# Works_007.net
KiCad netlist of a schematic drawn in EAGLE
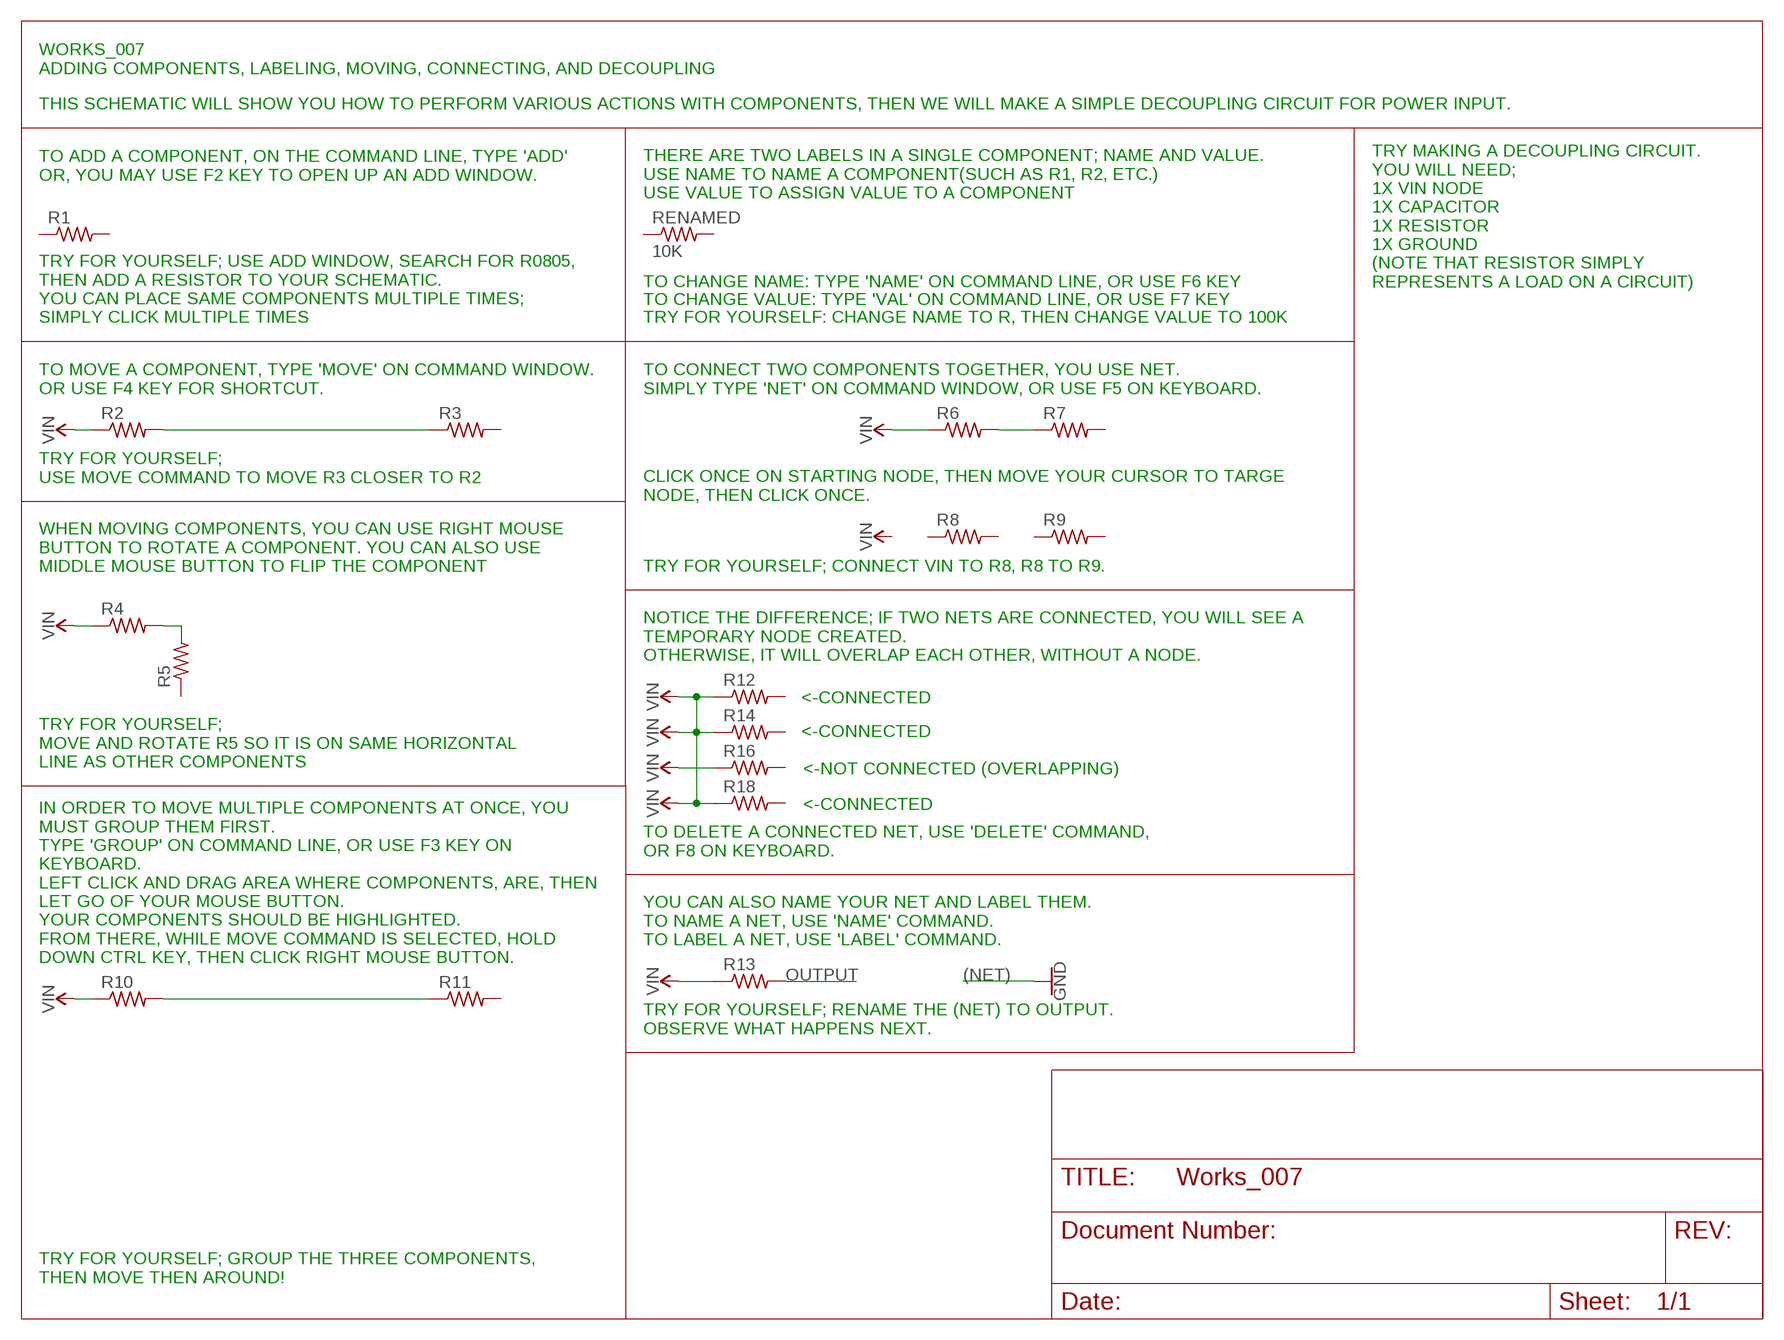
[diagram p0: schematic, sheet 1]

(export (version "E")
  (design (tool "Eeschema 10.0.6"))
  (components
    (comp (ref "R1")
      (value "R-US_R0805")
      (footprint "eagle-import:R0805")
      (libsource (lib "eagle-import") (part "R-US_R0805"))
    )
    (comp (ref "R2")
      (value "R-US_R0805")
      (footprint "eagle-import:R0805")
      (libsource (lib "eagle-import") (part "R-US_R0805"))
    )
    (comp (ref "R3")
      (value "R-US_R0805")
      (footprint "eagle-import:R0805")
      (libsource (lib "eagle-import") (part "R-US_R0805"))
    )
    (comp (ref "R4")
      (value "R-US_R0805")
      (footprint "eagle-import:R0805")
      (libsource (lib "eagle-import") (part "R-US_R0805"))
    )
    (comp (ref "R5")
      (value "R-US_R0805")
      (footprint "eagle-import:R0805")
      (libsource (lib "eagle-import") (part "R-US_R0805"))
    )
    (comp (ref "R6")
      (value "R-US_R0805")
      (footprint "eagle-import:R0805")
      (libsource (lib "eagle-import") (part "R-US_R0805"))
    )
    (comp (ref "R7")
      (value "R-US_R0805")
      (footprint "eagle-import:R0805")
      (libsource (lib "eagle-import") (part "R-US_R0805"))
    )
    (comp (ref "R8")
      (value "R-US_R0805")
      (footprint "eagle-import:R0805")
      (libsource (lib "eagle-import") (part "R-US_R0805"))
    )
    (comp (ref "R9")
      (value "R-US_R0805")
      (footprint "eagle-import:R0805")
      (libsource (lib "eagle-import") (part "R-US_R0805"))
    )
    (comp (ref "R10")
      (value "R-US_R0805")
      (footprint "eagle-import:R0805")
      (libsource (lib "eagle-import") (part "R-US_R0805"))
    )
    (comp (ref "R11")
      (value "R-US_R0805")
      (footprint "eagle-import:R0805")
      (libsource (lib "eagle-import") (part "R-US_R0805"))
    )
    (comp (ref "R12")
      (value "R-US_R0805")
      (footprint "eagle-import:R0805")
      (libsource (lib "eagle-import") (part "R-US_R0805"))
    )
    (comp (ref "R13")
      (value "R-US_R0805")
      (footprint "eagle-import:R0805")
      (libsource (lib "eagle-import") (part "R-US_R0805"))
    )
    (comp (ref "R14")
      (value "R-US_R0805")
      (footprint "eagle-import:R0805")
      (libsource (lib "eagle-import") (part "R-US_R0805"))
    )
    (comp (ref "R16")
      (value "R-US_R0805")
      (footprint "eagle-import:R0805")
      (libsource (lib "eagle-import") (part "R-US_R0805"))
    )
    (comp (ref "R18")
      (value "R-US_R0805")
      (footprint "eagle-import:R0805")
      (libsource (lib "eagle-import") (part "R-US_R0805"))
    )
    (comp (ref "RENAMED")
      (value "10K")
      (footprint "eagle-import:R0805")
      (libsource (lib "eagle-import") (part "R-US_R0805"))
    )
  )
  (nets
    (net (code "1") (name "/OUTPUT") (class "Default")
      (node (ref "R13") (pin "2") (pinfunction "2_2") (pintype "passive"))
    )
    (net (code "3") (name "Net-(R2-Pad2)") (class "Default")
      (node (ref "R2") (pin "2") (pinfunction "2_2") (pintype "passive"))
      (node (ref "R3") (pin "1") (pinfunction "1_1") (pintype "passive"))
    )
    (net (code "4") (name "Net-(R4-Pad2)") (class "Default")
      (node (ref "R4") (pin "2") (pinfunction "2_2") (pintype "passive"))
      (node (ref "R5") (pin "2") (pinfunction "2_2") (pintype "passive"))
    )
    (net (code "5") (name "Net-(R6-Pad2)") (class "Default")
      (node (ref "R6") (pin "2") (pinfunction "2_2") (pintype "passive"))
      (node (ref "R7") (pin "1") (pinfunction "1_1") (pintype "passive"))
    )
    (net (code "6") (name "Net-(R10-Pad2)") (class "Default")
      (node (ref "R10") (pin "2") (pinfunction "2_2") (pintype "passive"))
      (node (ref "R11") (pin "1") (pinfunction "1_1") (pintype "passive"))
    )
    (net (code "7") (name "VIN") (class "Default")
      (node (ref "R10") (pin "1") (pinfunction "1_1") (pintype "passive"))
      (node (ref "R12") (pin "1") (pinfunction "1_1") (pintype "passive"))
      (node (ref "R13") (pin "1") (pinfunction "1_1") (pintype "passive"))
      (node (ref "R14") (pin "1") (pinfunction "1_1") (pintype "passive"))
      (node (ref "R16") (pin "1") (pinfunction "1_1") (pintype "passive"))
      (node (ref "R18") (pin "1") (pinfunction "1_1") (pintype "passive"))
      (node (ref "R2") (pin "1") (pinfunction "1_1") (pintype "passive"))
      (node (ref "R4") (pin "1") (pinfunction "1_1") (pintype "passive"))
      (node (ref "R6") (pin "1") (pinfunction "1_1") (pintype "passive"))
    )
    (net (code "8") (name "unconnected-(R1-Pad1)") (class "Default")
      (node (ref "R1") (pin "1") (pinfunction "1_1") (pintype "passive"))
    )
    (net (code "9") (name "unconnected-(R1-Pad2)") (class "Default")
      (node (ref "R1") (pin "2") (pinfunction "2_2") (pintype "passive"))
    )
    (net (code "10") (name "unconnected-(R3-Pad2)") (class "Default")
      (node (ref "R3") (pin "2") (pinfunction "2_2") (pintype "passive"))
    )
    (net (code "11") (name "unconnected-(R5-Pad1)") (class "Default")
      (node (ref "R5") (pin "1") (pinfunction "1_1") (pintype "passive"))
    )
    (net (code "12") (name "unconnected-(R7-Pad2)") (class "Default")
      (node (ref "R7") (pin "2") (pinfunction "2_2") (pintype "passive"))
    )
    (net (code "13") (name "unconnected-(R8-Pad1)") (class "Default")
      (node (ref "R8") (pin "1") (pinfunction "1_1") (pintype "passive"))
    )
    (net (code "14") (name "unconnected-(R8-Pad2)") (class "Default")
      (node (ref "R8") (pin "2") (pinfunction "2_2") (pintype "passive"))
    )
    (net (code "15") (name "unconnected-(R9-Pad1)") (class "Default")
      (node (ref "R9") (pin "1") (pinfunction "1_1") (pintype "passive"))
    )
    (net (code "16") (name "unconnected-(R9-Pad2)") (class "Default")
      (node (ref "R9") (pin "2") (pinfunction "2_2") (pintype "passive"))
    )
    (net (code "17") (name "unconnected-(R11-Pad2)") (class "Default")
      (node (ref "R11") (pin "2") (pinfunction "2_2") (pintype "passive"))
    )
    (net (code "18") (name "unconnected-(R12-Pad2)") (class "Default")
      (node (ref "R12") (pin "2") (pinfunction "2_2") (pintype "passive"))
    )
    (net (code "19") (name "unconnected-(R14-Pad2)") (class "Default")
      (node (ref "R14") (pin "2") (pinfunction "2_2") (pintype "passive"))
    )
    (net (code "20") (name "unconnected-(R16-Pad2)") (class "Default")
      (node (ref "R16") (pin "2") (pinfunction "2_2") (pintype "passive"))
    )
    (net (code "21") (name "unconnected-(R18-Pad2)") (class "Default")
      (node (ref "R18") (pin "2") (pinfunction "2_2") (pintype "passive"))
    )
    (net (code "22") (name "unconnected-(RENAMED-Pad1)") (class "Default")
      (node (ref "RENAMED") (pin "1") (pinfunction "1_1") (pintype "passive"))
    )
    (net (code "23") (name "unconnected-(RENAMED-Pad2)") (class "Default")
      (node (ref "RENAMED") (pin "2") (pinfunction "2_2") (pintype "passive"))
    )
  )
)
